# treehopper-micro.net
KiCad netlist of a schematic drawn in Altium Designer
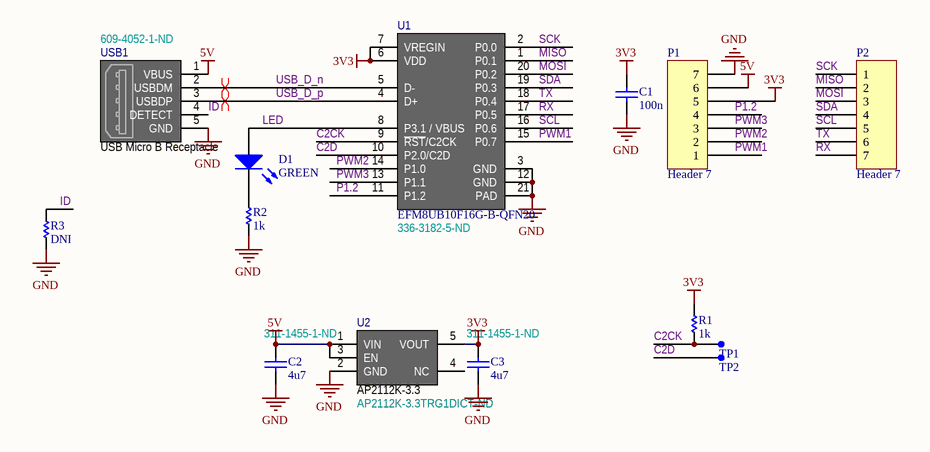
[diagram p0: treehopper-micro.SchDoc]

(export (version "E")
  (design (tool "Eeschema 10.0.6"))
  (components
    (comp (ref "C1")
      (value "100n")
      (footprint "CAPC1005N")
      (description "Capacitor (Semiconductor SIM Model)")
      (fields (field (name "PUBLISHER") "Altium Limited"))
      (libsource (lib "Miscellaneous Devices") (part "Cap Semi"))
    )
    (comp (ref "C2")
      (value "4u7")
      (footprint "CAPC1608N")
      (description "CAP SEMI 4U7 10V 0603")
      (fields
        (field (name "SUPPLIER PART NUMBER 1") "311-1455-1-ND")
        (field (name "PUBLISHER") "Altium Limited")
      )
      (libsource (lib "Miscellaneous Devices") (part "Cap Semi"))
    )
    (comp (ref "C3")
      (value "4u7")
      (footprint "CAPC1608N")
      (description "CAP SEMI 4U7 10V 0603")
      (fields
        (field (name "SUPPLIER PART NUMBER 1") "311-1455-1-ND")
        (field (name "PUBLISHER") "Altium Limited")
      )
      (libsource (lib "Miscellaneous Devices") (part "Cap Semi"))
    )
    (comp (ref "D1")
      (value "GREEN")
      (footprint "LTST-C190GKT_NO_SILK")
      (description "Typical greenGaAs LED")
      (fields (field (name "PUBLISHER") "Altium Limited"))
      (libsource (lib "Miscellaneous Devices") (part "LED_GREEN"))
    )
    (comp (ref "P1")
      (value "Header 7")
      (footprint "HDR1X7_CASTELATED")
      (description "Header, 7-Pin")
      (fields (field (name "PUBLISHER") "Altium Limited"))
      (libsource (lib "") (part "Header 7_1"))
    )
    (comp (ref "P2")
      (value "Header 7")
      (footprint "HDR1X7_CASTELATED")
      (description "Header, 7-Pin")
      (fields (field (name "PUBLISHER") "Altium Limited"))
      (libsource (lib "Miscellaneous Connectors") (part "Header 7"))
    )
    (comp (ref "R1")
      (value "1k")
      (footprint "RESC1005N")
      (description "Semiconductor Resistor")
      (fields (field (name "PUBLISHER") "Altium Limited"))
      (libsource (lib "Miscellaneous Devices") (part "Res Semi"))
    )
    (comp (ref "R2")
      (value "1k")
      (footprint "RESC1005N")
      (description "Semiconductor Resistor")
      (fields (field (name "PUBLISHER") "Altium Limited"))
      (libsource (lib "Miscellaneous Devices") (part "Res Semi"))
    )
    (comp (ref "R3")
      (value "DNI")
      (footprint "RESC1005N_TIE")
      (description "Semiconductor Resistor")
      (fields (field (name "PUBLISHER") "Altium Limited"))
      (libsource (lib "Miscellaneous Devices") (part "Res Semi"))
    )
    (comp (ref "TP1")
      (value "TESTPOINT")
      (footprint "TESTPOINT100")
      (description "Testpoint")
      (fields (field (name "PUBLISHER") "Altium Limited"))
      (libsource (lib "Miscellaneous Connectors") (part "TESTPOINT"))
    )
    (comp (ref "TP2")
      (value "TESTPOINT")
      (footprint "TESTPOINT100")
      (description "Testpoint")
      (fields (field (name "PUBLISHER") "Altium Limited"))
      (libsource (lib "Miscellaneous Connectors") (part "TESTPOINT"))
    )
    (comp (ref "U1")
      (value "EFM8UB10F16G-B-QFN20")
      (footprint "QFN50P300X300X90-20N")
      (description "IC MCU 16KB 20QFN")
      (fields
        (field (name "MANUFACTURER") "Silicon Labs")
        (field (name "SUPPLIER PART NUMBER 1") "336-3182-5-ND")
      )
      (libsource (lib "SiLabs EFM8 MCU") (part "EFM8UB10F16G-B-QFN20"))
    )
    (comp (ref "U2")
      (value "AP2112K-3.3")
      (footprint "SOT23-5AN-no-silk")
      (description "AP2112 IC REG LDO 3.3V 0.6A SOT25")
      (fields
        (field (name "MANUFACTURER") "Diodes Incorporated")
        (field (name "MANUFACTURER PART NUMBER") "AP2112K-3.3TRG1")
        (field (name "SUPPLIER PART NUMBER 1") "AP2112K-3.3TRG1DICT-ND")
      )
      (libsource (lib "Diodes Inc LDO Regulator") (part "AP2112K-3.3"))
    )
    (comp (ref "USB1")
      (value "USB Micro B Receptacle")
      (footprint "ZX60-B-5S(01)")
      (fields (field (name "SUPPLIER PART NUMBER 1") "609-4052-1-ND"))
      (libsource (lib "Miscellaneous Connectors") (part "USB Micro B Receptacle"))
    )
  )
  (nets
    (net (code "1") (name "/C2CK") (class "Default")
      (node (ref "R1") (pin "1") (pinfunction "1_1") (pintype "passive"))
      (node (ref "TP1") (pin "1") (pinfunction "TP_1") (pintype "passive"))
      (node (ref "U1") (pin "9") (pinfunction "~{RST}/C2CK_9") (pintype "passive"))
    )
    (net (code "2") (name "/C2D") (class "Default")
      (node (ref "TP2") (pin "1") (pinfunction "TP_1") (pintype "passive"))
      (node (ref "U1") (pin "10") (pinfunction "P2.0/C2D_10") (pintype "passive"))
    )
    (net (code "3") (name "/ID") (class "Default")
      (node (ref "R3") (pin "2") (pinfunction "2_2") (pintype "passive"))
      (node (ref "USB1") (pin "4") (pinfunction "DETECT_4") (pintype "power_in"))
    )
    (net (code "4") (name "/LED") (class "Default")
      (node (ref "D1") (pin "1") (pinfunction "A_1") (pintype "passive"))
      (node (ref "U1") (pin "8") (pinfunction "P3.1_/_VBUS_8") (pintype "passive"))
    )
    (net (code "5") (name "/MISO") (class "Default")
      (node (ref "P2") (pin "2") (pinfunction "2_2") (pintype "passive"))
      (node (ref "U1") (pin "1") (pinfunction "P0.1_1") (pintype "passive"))
    )
    (net (code "6") (name "/MOSI") (class "Default")
      (node (ref "P2") (pin "3") (pinfunction "3_3") (pintype "passive"))
      (node (ref "U1") (pin "20") (pinfunction "P0.2_20") (pintype "passive"))
    )
    (net (code "7") (name "/P1.2") (class "Default")
      (node (ref "P1") (pin "4") (pinfunction "4_4") (pintype "passive"))
      (node (ref "U1") (pin "11") (pinfunction "P1.2_11") (pintype "passive"))
    )
    (net (code "8") (name "/PWM1") (class "Default")
      (node (ref "P1") (pin "1") (pinfunction "1_1") (pintype "passive"))
      (node (ref "U1") (pin "15") (pinfunction "P0.7_15") (pintype "passive"))
    )
    (net (code "9") (name "/PWM2") (class "Default")
      (node (ref "P1") (pin "2") (pinfunction "2_2") (pintype "passive"))
      (node (ref "U1") (pin "14") (pinfunction "P1.0_14") (pintype "passive"))
    )
    (net (code "10") (name "/PWM3") (class "Default")
      (node (ref "P1") (pin "3") (pinfunction "3_3") (pintype "passive"))
      (node (ref "U1") (pin "13") (pinfunction "P1.1_13") (pintype "passive"))
    )
    (net (code "11") (name "/RX") (class "Default")
      (node (ref "P2") (pin "7") (pinfunction "7_7") (pintype "passive"))
      (node (ref "U1") (pin "17") (pinfunction "P0.5_17") (pintype "passive"))
    )
    (net (code "12") (name "/SCK") (class "Default")
      (node (ref "P2") (pin "1") (pinfunction "1_1") (pintype "passive"))
      (node (ref "U1") (pin "2") (pinfunction "P0.0_2") (pintype "passive"))
    )
    (net (code "13") (name "/SCL") (class "Default")
      (node (ref "P2") (pin "5") (pinfunction "5_5") (pintype "passive"))
      (node (ref "U1") (pin "16") (pinfunction "P0.6_16") (pintype "passive"))
    )
    (net (code "14") (name "/SDA") (class "Default")
      (node (ref "P2") (pin "4") (pinfunction "4_4") (pintype "passive"))
      (node (ref "U1") (pin "19") (pinfunction "P0.3_19") (pintype "passive"))
    )
    (net (code "15") (name "/TX") (class "Default")
      (node (ref "P2") (pin "6") (pinfunction "6_6") (pintype "passive"))
      (node (ref "U1") (pin "18") (pinfunction "P0.4_18") (pintype "passive"))
    )
    (net (code "16") (name "/USB_D_n") (class "Default")
      (node (ref "U1") (pin "5") (pinfunction "D-_5") (pintype "passive"))
      (node (ref "USB1") (pin "2") (pinfunction "USBDM_2") (pintype "power_in"))
    )
    (net (code "17") (name "/USB_D_p") (class "Default")
      (node (ref "U1") (pin "4") (pinfunction "D+_4") (pintype "passive"))
      (node (ref "USB1") (pin "3") (pinfunction "USBDP_3") (pintype "power_in"))
    )
    (net (code "18") (name "3V3") (class "Default")
      (node (ref "C1") (pin "2") (pinfunction "2_2") (pintype "passive"))
      (node (ref "C3") (pin "2") (pinfunction "2_2") (pintype "passive"))
      (node (ref "P1") (pin "5") (pinfunction "5_5") (pintype "passive"))
      (node (ref "R1") (pin "2") (pinfunction "2_2") (pintype "passive"))
      (node (ref "U1") (pin "6") (pinfunction "VDD_6") (pintype "passive"))
      (node (ref "U1") (pin "7") (pinfunction "VREGIN_7") (pintype "passive"))
      (node (ref "U2") (pin "5") (pinfunction "VOUT_5") (pintype "passive"))
    )
    (net (code "19") (name "5V") (class "Default")
      (node (ref "C2") (pin "2") (pinfunction "2_2") (pintype "passive"))
      (node (ref "P1") (pin "6") (pinfunction "6_6") (pintype "passive"))
      (node (ref "U2") (pin "1") (pinfunction "VIN_1") (pintype "passive"))
      (node (ref "U2") (pin "3") (pinfunction "EN_3") (pintype "passive"))
      (node (ref "USB1") (pin "1") (pinfunction "VBUS_1") (pintype "power_in"))
    )
    (net (code "20") (name "GND") (class "Default")
      (node (ref "C1") (pin "1") (pinfunction "1_1") (pintype "passive"))
      (node (ref "C2") (pin "1") (pinfunction "1_1") (pintype "passive"))
      (node (ref "C3") (pin "1") (pinfunction "1_1") (pintype "passive"))
      (node (ref "P1") (pin "7") (pinfunction "7_7") (pintype "passive"))
      (node (ref "R2") (pin "1") (pinfunction "1_1") (pintype "passive"))
      (node (ref "R3") (pin "1") (pinfunction "1_1") (pintype "passive"))
      (node (ref "U1") (pin "12") (pinfunction "GND_12") (pintype "passive"))
      (node (ref "U1") (pin "21") (pinfunction "PAD_21") (pintype "passive"))
      (node (ref "U1") (pin "3") (pinfunction "GND_3") (pintype "passive"))
      (node (ref "U2") (pin "2") (pinfunction "GND_2") (pintype "passive"))
      (node (ref "USB1") (pin "5") (pinfunction "GND_5") (pintype "power_in"))
    )
    (net (code "21") (name "Net-(D1-K)") (class "Default")
      (node (ref "D1") (pin "2") (pinfunction "K_2") (pintype "passive"))
      (node (ref "R2") (pin "2") (pinfunction "2_2") (pintype "passive"))
    )
    (net (code "22") (name "unconnected-(U2-NC-Pad4)") (class "Default")
      (node (ref "U2") (pin "4") (pinfunction "NC_4") (pintype "passive"))
    )
  )
)
